# ArduinoFio.net
KiCad netlist of a schematic drawn in EAGLE
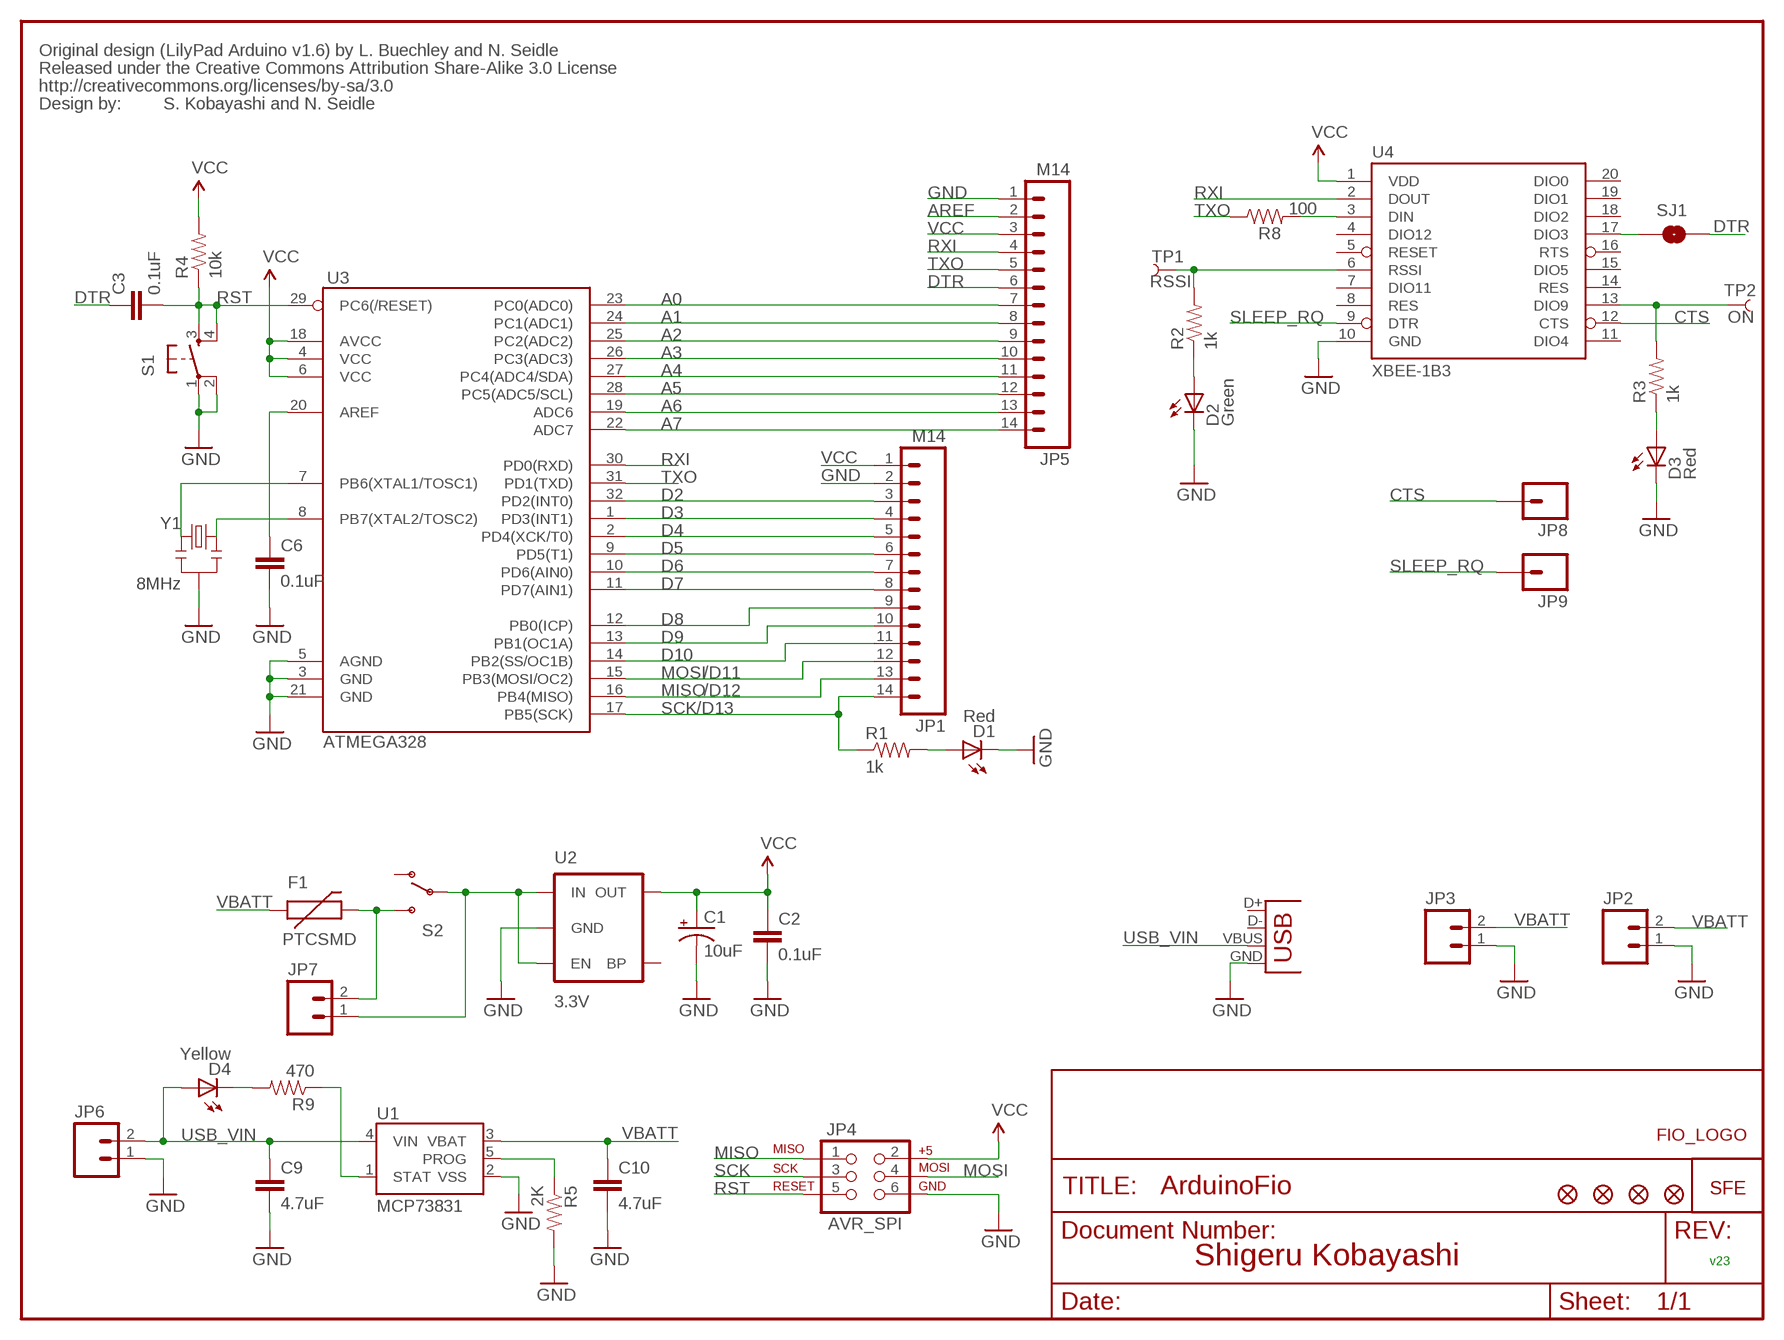
[diagram p0: schematic, sheet 1]

(export (version "E")
  (design (tool "Eeschema 10.0.6"))
  (components
    (comp (ref "C1")
      (value "10uF")
      (footprint "eagle-import:EIA3216")
      (libsource (lib "eagle-import") (part "CAP_POL1206"))
    )
    (comp (ref "C2")
      (value "0.1uF")
      (footprint "eagle-import:0402-CAP")
      (libsource (lib "eagle-import") (part "CAP0402-CAP"))
    )
    (comp (ref "C3")
      (value "0.1uF")
      (footprint "eagle-import:0402-CAP")
      (libsource (lib "eagle-import") (part "CAP0402-CAP"))
    )
    (comp (ref "C6")
      (value "0.1uF")
      (footprint "eagle-import:0402-CAP")
      (libsource (lib "eagle-import") (part "CAP0402-CAP"))
    )
    (comp (ref "C9")
      (value "4.7uF")
      (footprint "eagle-import:0402-CAP")
      (libsource (lib "eagle-import") (part "CAP0402-CAP"))
    )
    (comp (ref "C10")
      (value "4.7uF")
      (footprint "eagle-import:0402-CAP")
      (libsource (lib "eagle-import") (part "CAP0402-CAP"))
    )
    (comp (ref "D1")
      (value "Red")
      (footprint "eagle-import:LED-0603")
      (libsource (lib "eagle-import") (part "LED0603"))
    )
    (comp (ref "D2")
      (value "Green")
      (footprint "eagle-import:LED-0603")
      (libsource (lib "eagle-import") (part "LED0603"))
    )
    (comp (ref "D3")
      (value "Red")
      (footprint "eagle-import:LED-0603")
      (libsource (lib "eagle-import") (part "LED0603"))
    )
    (comp (ref "D4")
      (value "Yellow")
      (footprint "eagle-import:LED-0603")
      (libsource (lib "eagle-import") (part "LED0603"))
    )
    (comp (ref "F1")
      (value "PTCSMD")
      (footprint "eagle-import:PTC-1206")
      (libsource (lib "eagle-import") (part "PTCSMD"))
    )
    (comp (ref "FD1")
      (value "FIDUCIAL1X2")
      (footprint "eagle-import:FIDUCIAL-1X2")
      (libsource (lib "eagle-import") (part "SparkFun-Aesthetics_FIDUCIAL1X2"))
    )
    (comp (ref "FD2")
      (value "FIDUCIAL1X2")
      (footprint "eagle-import:FIDUCIAL-1X2")
      (libsource (lib "eagle-import") (part "SparkFun-Aesthetics_FIDUCIAL1X2"))
    )
    (comp (ref "JP1")
      (value "M14")
      (footprint "eagle-import:1X14")
      (libsource (lib "eagle-import") (part "M14"))
    )
    (comp (ref "JP2")
      (value "M02PTH")
      (footprint "eagle-import:1X02")
      (libsource (lib "eagle-import") (part "M02PTH"))
    )
    (comp (ref "JP3")
      (value "M02-JST-2MM-SMT")
      (footprint "eagle-import:JST-2-SMD")
      (libsource (lib "eagle-import") (part "M02-JST-2MM-SMT"))
    )
    (comp (ref "JP4")
      (value "AVR_SPI")
      (footprint "eagle-import:2X3")
      (libsource (lib "eagle-import") (part "AVR_SPI_PRG_6PTH"))
    )
    (comp (ref "JP5")
      (value "M14")
      (footprint "eagle-import:1X14")
      (libsource (lib "eagle-import") (part "M14"))
    )
    (comp (ref "JP6")
      (value "M02PTH")
      (footprint "eagle-import:1X02")
      (libsource (lib "eagle-import") (part "M02PTH"))
    )
    (comp (ref "JP7")
      (value "M02PTH")
      (footprint "eagle-import:1X02")
      (libsource (lib "eagle-import") (part "M02PTH"))
    )
    (comp (ref "JP8")
      (value "M01PTH")
      (footprint "eagle-import:1X01")
      (libsource (lib "eagle-import") (part "M01PTH"))
    )
    (comp (ref "JP9")
      (value "M01PTH")
      (footprint "eagle-import:1X01")
      (libsource (lib "eagle-import") (part "M01PTH"))
    )
    (comp (ref "R1")
      (value "1k")
      (footprint "eagle-import:0402-RES")
      (libsource (lib "eagle-import") (part "RESISTOR0402-RES"))
    )
    (comp (ref "R2")
      (value "1k")
      (footprint "eagle-import:0402-RES")
      (libsource (lib "eagle-import") (part "RESISTOR0402-RES"))
    )
    (comp (ref "R3")
      (value "1k")
      (footprint "eagle-import:0402-RES")
      (libsource (lib "eagle-import") (part "RESISTOR0402-RES"))
    )
    (comp (ref "R4")
      (value "10k")
      (footprint "eagle-import:0402-RES")
      (libsource (lib "eagle-import") (part "RESISTOR0402-RES"))
    )
    (comp (ref "R5")
      (value "2K")
      (footprint "eagle-import:0402-RES")
      (libsource (lib "eagle-import") (part "RESISTOR0402-RES"))
    )
    (comp (ref "R8")
      (value "100")
      (footprint "eagle-import:0402-RES")
      (libsource (lib "eagle-import") (part "RESISTOR0402-RES"))
    )
    (comp (ref "R9")
      (value "470")
      (footprint "eagle-import:0402-RES")
      (libsource (lib "eagle-import") (part "RESISTOR0402-RES"))
    )
    (comp (ref "S1")
      (value "TAC_SWITCHSMD")
      (footprint "eagle-import:TACTILE_SWITCH_SMD")
      (libsource (lib "eagle-import") (part "TAC_SWITCHSMD"))
    )
    (comp (ref "S2")
      (value "SWITCH-SPSTSMD")
      (footprint "eagle-import:AYZ0202")
      (libsource (lib "eagle-import") (part "SWITCH-SPSTSMD"))
    )
    (comp (ref "SJ1")
      (value "SOLDERJUMPERNC")
      (footprint "eagle-import:SJ_2S")
      (libsource (lib "eagle-import") (part "SOLDERJUMPERNC"))
    )
    (comp (ref "TP1")
      (value "RSSI")
      (footprint "eagle-import:PAD.03X.05")
      (libsource (lib "eagle-import") (part "TEST-POINT3X5"))
    )
    (comp (ref "TP2")
      (value "ON")
      (footprint "eagle-import:PAD.03X.05")
      (libsource (lib "eagle-import") (part "TEST-POINT3X5"))
    )
    (comp (ref "U$1")
      (value "LOGO-SFENEW")
      (footprint "eagle-import:SFE-NEW-WEBLOGO")
      (libsource (lib "eagle-import") (part "LOGO-SFENEW"))
    )
    (comp (ref "U$3")
      (value "CREATIVE_COMMONS")
      (footprint "eagle-import:CREATIVE_COMMONS")
      (libsource (lib "eagle-import") (part "CREATIVE_COMMONS"))
    )
    (comp (ref "U$4")
      (value "FIDUCIAL1X2")
      (footprint "eagle-import:FIDUCIAL-1X2")
      (libsource (lib "eagle-import") (part "FIDUCIAL1X2"))
    )
    (comp (ref "U$5")
      (value "FIDUCIAL1X2")
      (footprint "eagle-import:FIDUCIAL-1X2")
      (libsource (lib "eagle-import") (part "FIDUCIAL1X2"))
    )
    (comp (ref "U$6")
      (value "FIO_LOGOV2")
      (footprint "eagle-import:FUNNEL_LOGO_BOTTOM_V2")
      (libsource (lib "eagle-import") (part "FIO_LOGOV2"))
    )
    (comp (ref "U1")
      (value "MCP73831")
      (footprint "eagle-import:SOT23-5")
      (libsource (lib "eagle-import") (part "MCP73831SMD"))
    )
    (comp (ref "U2")
      (value "3.3V")
      (footprint "eagle-import:SOT23-5")
      (libsource (lib "eagle-import") (part "V_REG_LDOSMD"))
    )
    (comp (ref "U3")
      (value "ATMEGA328")
      (footprint "eagle-import:TQFP32-08")
      (libsource (lib "eagle-import") (part "ATMEGA168"))
    )
    (comp (ref "U4")
      (value "XBEE-1B3")
      (footprint "eagle-import:XBEE-SMD")
      (libsource (lib "eagle-import") (part "XBEE-1B3"))
    )
    (comp (ref "X1")
      (value "USBSMD")
      (footprint "eagle-import:USB-MINIB")
      (libsource (lib "eagle-import") (part "USBSMD"))
    )
    (comp (ref "Y1")
      (value "8MHz")
      (footprint "eagle-import:RESONATOR-SMD")
      (libsource (lib "eagle-import") (part "RESONATORSMD"))
    )
  )
  (nets
    (net (code "1") (name "/A0") (class "Default")
      (node (ref "JP5") (pin "7") (pinfunction "7_7") (pintype "passive"))
      (node (ref "U3") (pin "23") (pinfunction "PC0(ADC0)_23") (pintype "bidirectional"))
    )
    (net (code "2") (name "/A1") (class "Default")
      (node (ref "JP5") (pin "8") (pinfunction "8_8") (pintype "passive"))
      (node (ref "U3") (pin "24") (pinfunction "PC1(ADC1)_24") (pintype "bidirectional"))
    )
    (net (code "3") (name "/A2") (class "Default")
      (node (ref "JP5") (pin "9") (pinfunction "9_9") (pintype "passive"))
      (node (ref "U3") (pin "25") (pinfunction "PC2(ADC2)_25") (pintype "bidirectional"))
    )
    (net (code "4") (name "/A3") (class "Default")
      (node (ref "JP5") (pin "10") (pinfunction "10_10") (pintype "passive"))
      (node (ref "U3") (pin "26") (pinfunction "PC3(ADC3)_26") (pintype "bidirectional"))
    )
    (net (code "5") (name "/A4") (class "Default")
      (node (ref "JP5") (pin "11") (pinfunction "11_11") (pintype "passive"))
      (node (ref "U3") (pin "27") (pinfunction "PC4(ADC4/SDA)_27") (pintype "bidirectional"))
    )
    (net (code "6") (name "/A5") (class "Default")
      (node (ref "JP5") (pin "12") (pinfunction "12_12") (pintype "passive"))
      (node (ref "U3") (pin "28") (pinfunction "PC5(ADC5/SCL)_28") (pintype "bidirectional"))
    )
    (net (code "7") (name "/A6") (class "Default")
      (node (ref "JP5") (pin "13") (pinfunction "13_13") (pintype "passive"))
      (node (ref "U3") (pin "19") (pinfunction "ADC6_19") (pintype "bidirectional"))
    )
    (net (code "8") (name "/A7") (class "Default")
      (node (ref "JP5") (pin "14") (pinfunction "14_14") (pintype "passive"))
      (node (ref "U3") (pin "22") (pinfunction "ADC7_22") (pintype "bidirectional"))
    )
    (net (code "9") (name "/AREF") (class "Default")
      (node (ref "C6") (pin "1") (pinfunction "1_1") (pintype "passive"))
      (node (ref "JP5") (pin "2") (pinfunction "2_2") (pintype "passive"))
      (node (ref "U3") (pin "20") (pinfunction "AREF_20") (pintype "bidirectional"))
    )
    (net (code "10") (name "/CTS") (class "Default")
      (node (ref "JP8") (pin "1") (pinfunction "1_1") (pintype "passive"))
      (node (ref "U4") (pin "12") (pinfunction "CTS_12") (pintype "output"))
    )
    (net (code "11") (name "/D2") (class "Default")
      (node (ref "JP1") (pin "3") (pinfunction "3_3") (pintype "passive"))
      (node (ref "U3") (pin "32") (pinfunction "PD2(INT0)_32") (pintype "bidirectional"))
    )
    (net (code "12") (name "/D3") (class "Default")
      (node (ref "JP1") (pin "4") (pinfunction "4_4") (pintype "passive"))
      (node (ref "U3") (pin "1") (pinfunction "PD3(INT1)_1") (pintype "bidirectional"))
    )
    (net (code "13") (name "/D4") (class "Default")
      (node (ref "JP1") (pin "5") (pinfunction "5_5") (pintype "passive"))
      (node (ref "U3") (pin "2") (pinfunction "PD4(XCK/T0)_2") (pintype "bidirectional"))
    )
    (net (code "14") (name "/D5") (class "Default")
      (node (ref "JP1") (pin "6") (pinfunction "6_6") (pintype "passive"))
      (node (ref "U3") (pin "9") (pinfunction "PD5(T1)_9") (pintype "bidirectional"))
    )
    (net (code "15") (name "/D6") (class "Default")
      (node (ref "JP1") (pin "7") (pinfunction "7_7") (pintype "passive"))
      (node (ref "U3") (pin "10") (pinfunction "PD6(AIN0)_10") (pintype "bidirectional"))
    )
    (net (code "16") (name "/D7") (class "Default")
      (node (ref "JP1") (pin "8") (pinfunction "8_8") (pintype "passive"))
      (node (ref "U3") (pin "11") (pinfunction "PD7(AIN1)_11") (pintype "bidirectional"))
    )
    (net (code "17") (name "/D8") (class "Default")
      (node (ref "JP1") (pin "9") (pinfunction "9_9") (pintype "passive"))
      (node (ref "U3") (pin "12") (pinfunction "PB0(ICP)_12") (pintype "bidirectional"))
    )
    (net (code "18") (name "/D9") (class "Default")
      (node (ref "JP1") (pin "10") (pinfunction "10_10") (pintype "passive"))
      (node (ref "U3") (pin "13") (pinfunction "PB1(OC1A)_13") (pintype "bidirectional"))
    )
    (net (code "19") (name "/D10") (class "Default")
      (node (ref "JP1") (pin "11") (pinfunction "11_11") (pintype "passive"))
      (node (ref "U3") (pin "14") (pinfunction "PB2(SS/OC1B)_14") (pintype "bidirectional"))
    )
    (net (code "20") (name "/DTR") (class "Default")
      (node (ref "C3") (pin "1") (pinfunction "1_1") (pintype "passive"))
      (node (ref "JP5") (pin "6") (pinfunction "6_6") (pintype "passive"))
      (node (ref "SJ1") (pin "2") (pinfunction "2_2") (pintype "passive"))
    )
    (net (code "21") (name "/MISO") (class "Default")
      (node (ref "JP1") (pin "13") (pinfunction "13_13") (pintype "passive"))
      (node (ref "JP4") (pin "1") (pinfunction "1_1") (pintype "passive"))
      (node (ref "U3") (pin "16") (pinfunction "PB4(MISO)_16") (pintype "bidirectional"))
    )
    (net (code "22") (name "/MOSI") (class "Default")
      (node (ref "JP1") (pin "12") (pinfunction "12_12") (pintype "passive"))
      (node (ref "JP4") (pin "4") (pinfunction "4_4") (pintype "passive"))
      (node (ref "U3") (pin "15") (pinfunction "PB3(MOSI/OC2)_15") (pintype "bidirectional"))
    )
    (net (code "23") (name "/RST") (class "Default")
      (node (ref "C3") (pin "2") (pinfunction "2_2") (pintype "passive"))
      (node (ref "JP4") (pin "5") (pinfunction "5_5") (pintype "passive"))
      (node (ref "R4") (pin "1") (pinfunction "1_1") (pintype "passive"))
      (node (ref "S1") (pin "3") (pinfunction "3_3") (pintype "passive"))
      (node (ref "S1") (pin "4") (pinfunction "4_4") (pintype "passive"))
      (node (ref "U3") (pin "29") (pinfunction "PC6(/RESET)_29") (pintype "bidirectional"))
    )
    (net (code "24") (name "/RXI") (class "Default")
      (node (ref "JP5") (pin "4") (pinfunction "4_4") (pintype "passive"))
      (node (ref "U3") (pin "30") (pinfunction "PD0(RXD)_30") (pintype "bidirectional"))
      (node (ref "U4") (pin "2") (pinfunction "DOUT_2") (pintype "output"))
    )
    (net (code "25") (name "/SCK") (class "Default")
      (node (ref "JP1") (pin "14") (pinfunction "14_14") (pintype "passive"))
      (node (ref "JP4") (pin "3") (pinfunction "3_3") (pintype "passive"))
      (node (ref "R1") (pin "1") (pinfunction "1_1") (pintype "passive"))
      (node (ref "U3") (pin "17") (pinfunction "PB5(SCK)_17") (pintype "bidirectional"))
    )
    (net (code "26") (name "/SLEEP_RQ") (class "Default")
      (node (ref "JP9") (pin "1") (pinfunction "1_1") (pintype "passive"))
      (node (ref "U4") (pin "9") (pinfunction "DTR_9") (pintype "bidirectional"))
    )
    (net (code "27") (name "/TXO") (class "Default")
      (node (ref "JP5") (pin "5") (pinfunction "5_5") (pintype "passive"))
      (node (ref "R8") (pin "1") (pinfunction "1_1") (pintype "passive"))
      (node (ref "U3") (pin "31") (pinfunction "PD1(TXD)_31") (pintype "bidirectional"))
    )
    (net (code "28") (name "/USB_VIN") (class "Default")
      (node (ref "C9") (pin "1") (pinfunction "1_1") (pintype "passive"))
      (node (ref "D4") (pin "A") (pinfunction "A_A") (pintype "passive"))
      (node (ref "JP6") (pin "2") (pinfunction "2_2") (pintype "passive"))
      (node (ref "U1") (pin "4") (pinfunction "VIN_4") (pintype "power_in"))
      (node (ref "X1") (pin "VBUS") (pinfunction "VBUS_VBUS") (pintype "bidirectional"))
    )
    (net (code "29") (name "/VBATT") (class "Default")
      (node (ref "C10") (pin "1") (pinfunction "1_1") (pintype "passive"))
      (node (ref "F1") (pin "1") (pinfunction "1_1") (pintype "bidirectional"))
      (node (ref "JP2") (pin "2") (pinfunction "2_2") (pintype "passive"))
      (node (ref "JP3") (pin "2") (pinfunction "2_2") (pintype "passive"))
      (node (ref "U1") (pin "3") (pinfunction "VBAT_3") (pintype "power_in"))
    )
    (net (code "30") (name "GND") (class "Default")
      (node (ref "C1") (pin "C") (pinfunction "-_C") (pintype "passive"))
      (node (ref "C10") (pin "2") (pinfunction "2_2") (pintype "passive"))
      (node (ref "C2") (pin "2") (pinfunction "2_2") (pintype "passive"))
      (node (ref "C6") (pin "2") (pinfunction "2_2") (pintype "passive"))
      (node (ref "C9") (pin "2") (pinfunction "2_2") (pintype "passive"))
      (node (ref "D1") (pin "C") (pinfunction "C_C") (pintype "passive"))
      (node (ref "D2") (pin "C") (pinfunction "C_C") (pintype "passive"))
      (node (ref "D3") (pin "C") (pinfunction "C_C") (pintype "passive"))
      (node (ref "JP1") (pin "2") (pinfunction "2_2") (pintype "passive"))
      (node (ref "JP2") (pin "1") (pinfunction "1_1") (pintype "passive"))
      (node (ref "JP3") (pin "1") (pinfunction "1_1") (pintype "passive"))
      (node (ref "JP4") (pin "6") (pinfunction "6_6") (pintype "passive"))
      (node (ref "JP5") (pin "1") (pinfunction "1_1") (pintype "passive"))
      (node (ref "JP6") (pin "1") (pinfunction "1_1") (pintype "passive"))
      (node (ref "R5") (pin "2") (pinfunction "2_2") (pintype "passive"))
      (node (ref "S1") (pin "1") (pinfunction "1_1") (pintype "passive"))
      (node (ref "S1") (pin "2") (pinfunction "2_2") (pintype "passive"))
      (node (ref "U1") (pin "2") (pinfunction "VSS_2") (pintype "power_in"))
      (node (ref "U2") (pin "2") (pinfunction "GND_2") (pintype "input"))
      (node (ref "U3") (pin "21") (pinfunction "GND_21") (pintype "bidirectional"))
      (node (ref "U3") (pin "3") (pinfunction "GND_3") (pintype "bidirectional"))
      (node (ref "U3") (pin "5") (pinfunction "AGND_5") (pintype "bidirectional"))
      (node (ref "U4") (pin "10") (pinfunction "GND_10") (pintype "power_in"))
      (node (ref "X1") (pin "GND") (pinfunction "GND_GND") (pintype "bidirectional"))
      (node (ref "Y1") (pin "2") (pinfunction "2_2") (pintype "passive"))
    )
    (net (code "31") (name "Net-(D1-PadA)") (class "Default")
      (node (ref "D1") (pin "A") (pinfunction "A_A") (pintype "passive"))
      (node (ref "R1") (pin "2") (pinfunction "2_2") (pintype "passive"))
    )
    (net (code "32") (name "Net-(D2-PadA)") (class "Default")
      (node (ref "D2") (pin "A") (pinfunction "A_A") (pintype "passive"))
      (node (ref "R2") (pin "1") (pinfunction "1_1") (pintype "passive"))
    )
    (net (code "33") (name "Net-(D3-PadA)") (class "Default")
      (node (ref "D3") (pin "A") (pinfunction "A_A") (pintype "passive"))
      (node (ref "R3") (pin "1") (pinfunction "1_1") (pintype "passive"))
    )
    (net (code "34") (name "Net-(D4-PadC)") (class "Default")
      (node (ref "D4") (pin "C") (pinfunction "C_C") (pintype "passive"))
      (node (ref "R9") (pin "2") (pinfunction "2_2") (pintype "passive"))
    )
    (net (code "35") (name "Net-(S2-P)") (class "Default")
      (node (ref "JP7") (pin "1") (pinfunction "1_1") (pintype "passive"))
      (node (ref "S2") (pin "2") (pinfunction "P_2") (pintype "passive"))
      (node (ref "U2") (pin "1") (pinfunction "IN_1") (pintype "input"))
      (node (ref "U2") (pin "3") (pinfunction "EN_3") (pintype "input"))
    )
    (net (code "36") (name "Net-(S2-S)") (class "Default")
      (node (ref "F1") (pin "2") (pinfunction "2_2") (pintype "bidirectional"))
      (node (ref "JP7") (pin "2") (pinfunction "2_2") (pintype "passive"))
      (node (ref "S2") (pin "3") (pinfunction "S_3") (pintype "passive"))
    )
    (net (code "37") (name "Net-(TP1-1)") (class "Default")
      (node (ref "R2") (pin "2") (pinfunction "2_2") (pintype "passive"))
      (node (ref "TP1") (pin "P$1") (pinfunction "1_P$1") (pintype "bidirectional"))
      (node (ref "U4") (pin "6") (pinfunction "RSSI_6") (pintype "bidirectional"))
    )
    (net (code "38") (name "Net-(TP2-1)") (class "Default")
      (node (ref "R3") (pin "2") (pinfunction "2_2") (pintype "passive"))
      (node (ref "TP2") (pin "P$1") (pinfunction "1_P$1") (pintype "bidirectional"))
      (node (ref "U4") (pin "13") (pinfunction "DIO9_13") (pintype "bidirectional"))
    )
    (net (code "39") (name "Net-(U1-PROG)") (class "Default")
      (node (ref "R5") (pin "1") (pinfunction "1_1") (pintype "passive"))
      (node (ref "U1") (pin "5") (pinfunction "PROG_5") (pintype "input"))
    )
    (net (code "40") (name "Net-(U1-STAT)") (class "Default")
      (node (ref "R9") (pin "1") (pinfunction "1_1") (pintype "passive"))
      (node (ref "U1") (pin "1") (pinfunction "STAT_1") (pintype "output"))
    )
    (net (code "41") (name "Net-(U3-PB6(XTAL1{slash}TOSC1))") (class "Default")
      (node (ref "U3") (pin "7") (pinfunction "PB6(XTAL1/TOSC1)_7") (pintype "bidirectional"))
      (node (ref "Y1") (pin "3") (pinfunction "3_3") (pintype "passive"))
    )
    (net (code "42") (name "Net-(U3-PB7(XTAL2{slash}TOSC2))") (class "Default")
      (node (ref "U3") (pin "8") (pinfunction "PB7(XTAL2/TOSC2)_8") (pintype "bidirectional"))
      (node (ref "Y1") (pin "1") (pinfunction "1_1") (pintype "passive"))
    )
    (net (code "43") (name "Net-(U4-DIN)") (class "Default")
      (node (ref "R8") (pin "2") (pinfunction "2_2") (pintype "passive"))
      (node (ref "U4") (pin "3") (pinfunction "DIN_3") (pintype "input"))
    )
    (net (code "44") (name "Net-(U4-DIO3)") (class "Default")
      (node (ref "SJ1") (pin "1") (pinfunction "1_1") (pintype "passive"))
      (node (ref "U4") (pin "17") (pinfunction "DIO3_17") (pintype "bidirectional"))
    )
    (net (code "45") (name "VCC") (class "Default")
      (node (ref "C1") (pin "A") (pinfunction "+_A") (pintype "passive"))
      (node (ref "C2") (pin "1") (pinfunction "1_1") (pintype "passive"))
      (node (ref "JP1") (pin "1") (pinfunction "1_1") (pintype "passive"))
      (node (ref "JP4") (pin "2") (pinfunction "2_2") (pintype "passive"))
      (node (ref "JP5") (pin "3") (pinfunction "3_3") (pintype "passive"))
      (node (ref "R4") (pin "2") (pinfunction "2_2") (pintype "passive"))
      (node (ref "U2") (pin "5") (pinfunction "OUT_5") (pintype "passive"))
      (node (ref "U3") (pin "18") (pinfunction "AVCC_18") (pintype "bidirectional"))
      (node (ref "U3") (pin "4") (pinfunction "VCC_4") (pintype "bidirectional"))
      (node (ref "U3") (pin "6") (pinfunction "VCC_6") (pintype "bidirectional"))
      (node (ref "U4") (pin "1") (pinfunction "VDD_1") (pintype "power_in"))
    )
    (net (code "46") (name "unconnected-(S2-O-Pad1)") (class "Default")
      (node (ref "S2") (pin "1") (pinfunction "O_1") (pintype "passive"))
    )
    (net (code "47") (name "unconnected-(U2-BP-Pad4)") (class "Default")
      (node (ref "U2") (pin "4") (pinfunction "BP_4") (pintype "input"))
    )
    (net (code "48") (name "unconnected-(U4-DIO0-Pad20)") (class "Default")
      (node (ref "U4") (pin "20") (pinfunction "DIO0_20") (pintype "bidirectional"))
    )
    (net (code "49") (name "unconnected-(U4-DIO1-Pad19)") (class "Default")
      (node (ref "U4") (pin "19") (pinfunction "DIO1_19") (pintype "bidirectional"))
    )
    (net (code "50") (name "unconnected-(U4-DIO2-Pad18)") (class "Default")
      (node (ref "U4") (pin "18") (pinfunction "DIO2_18") (pintype "bidirectional"))
    )
    (net (code "51") (name "unconnected-(U4-DIO4-Pad11)") (class "Default")
      (node (ref "U4") (pin "11") (pinfunction "DIO4_11") (pintype "bidirectional"))
    )
    (net (code "52") (name "unconnected-(U4-DIO5-Pad15)") (class "Default")
      (node (ref "U4") (pin "15") (pinfunction "DIO5_15") (pintype "bidirectional"))
    )
    (net (code "53") (name "unconnected-(U4-DIO11-Pad7)") (class "Default")
      (node (ref "U4") (pin "7") (pinfunction "DIO11_7") (pintype "bidirectional"))
    )
    (net (code "54") (name "unconnected-(U4-DIO12-Pad4)") (class "Default")
      (node (ref "U4") (pin "4") (pinfunction "DIO12_4") (pintype "bidirectional"))
    )
    (net (code "55") (name "unconnected-(U4-RES-Pad8)") (class "Default")
      (node (ref "U4") (pin "8") (pinfunction "RES_8") (pintype "bidirectional"))
    )
    (net (code "56") (name "unconnected-(U4-RES-Pad14)") (class "Default")
      (node (ref "U4") (pin "14") (pinfunction "RES_14") (pintype "bidirectional"))
    )
    (net (code "57") (name "unconnected-(U4-RESET-Pad5)") (class "Default")
      (node (ref "U4") (pin "5") (pinfunction "RESET_5") (pintype "input"))
    )
    (net (code "58") (name "unconnected-(U4-RTS-Pad16)") (class "Default")
      (node (ref "U4") (pin "16") (pinfunction "RTS_16") (pintype "input"))
    )
    (net (code "59") (name "unconnected-(X1-PadD+)") (class "Default")
      (node (ref "X1") (pin "D+") (pinfunction "D+_D+") (pintype "bidirectional"))
    )
    (net (code "60") (name "unconnected-(X1-PadD-)") (class "Default")
      (node (ref "X1") (pin "D-") (pinfunction "D-_D-") (pintype "bidirectional"))
    )
  )
)
